# daqbeagle_shield.net
KiCad netlist of a schematic drawn in EAGLE
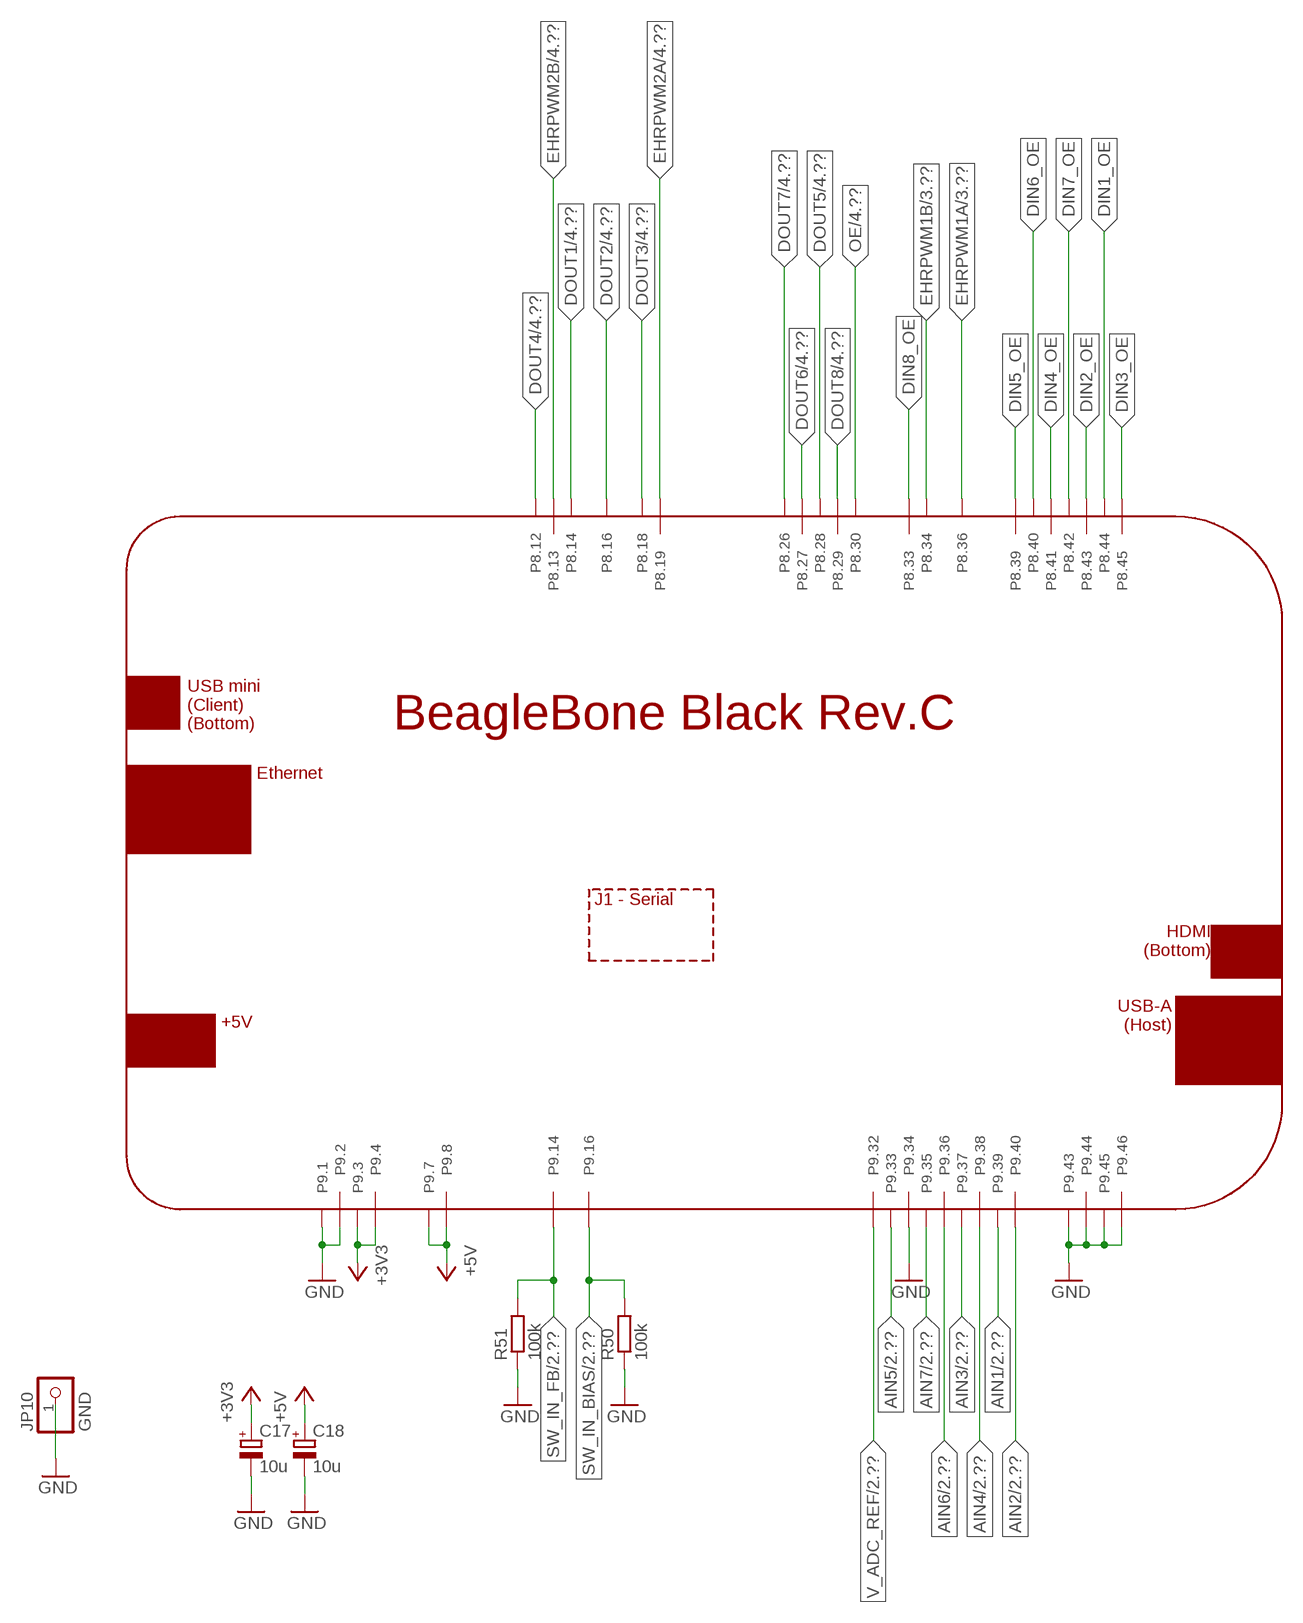
[diagram p0: schematic, sheet 1]
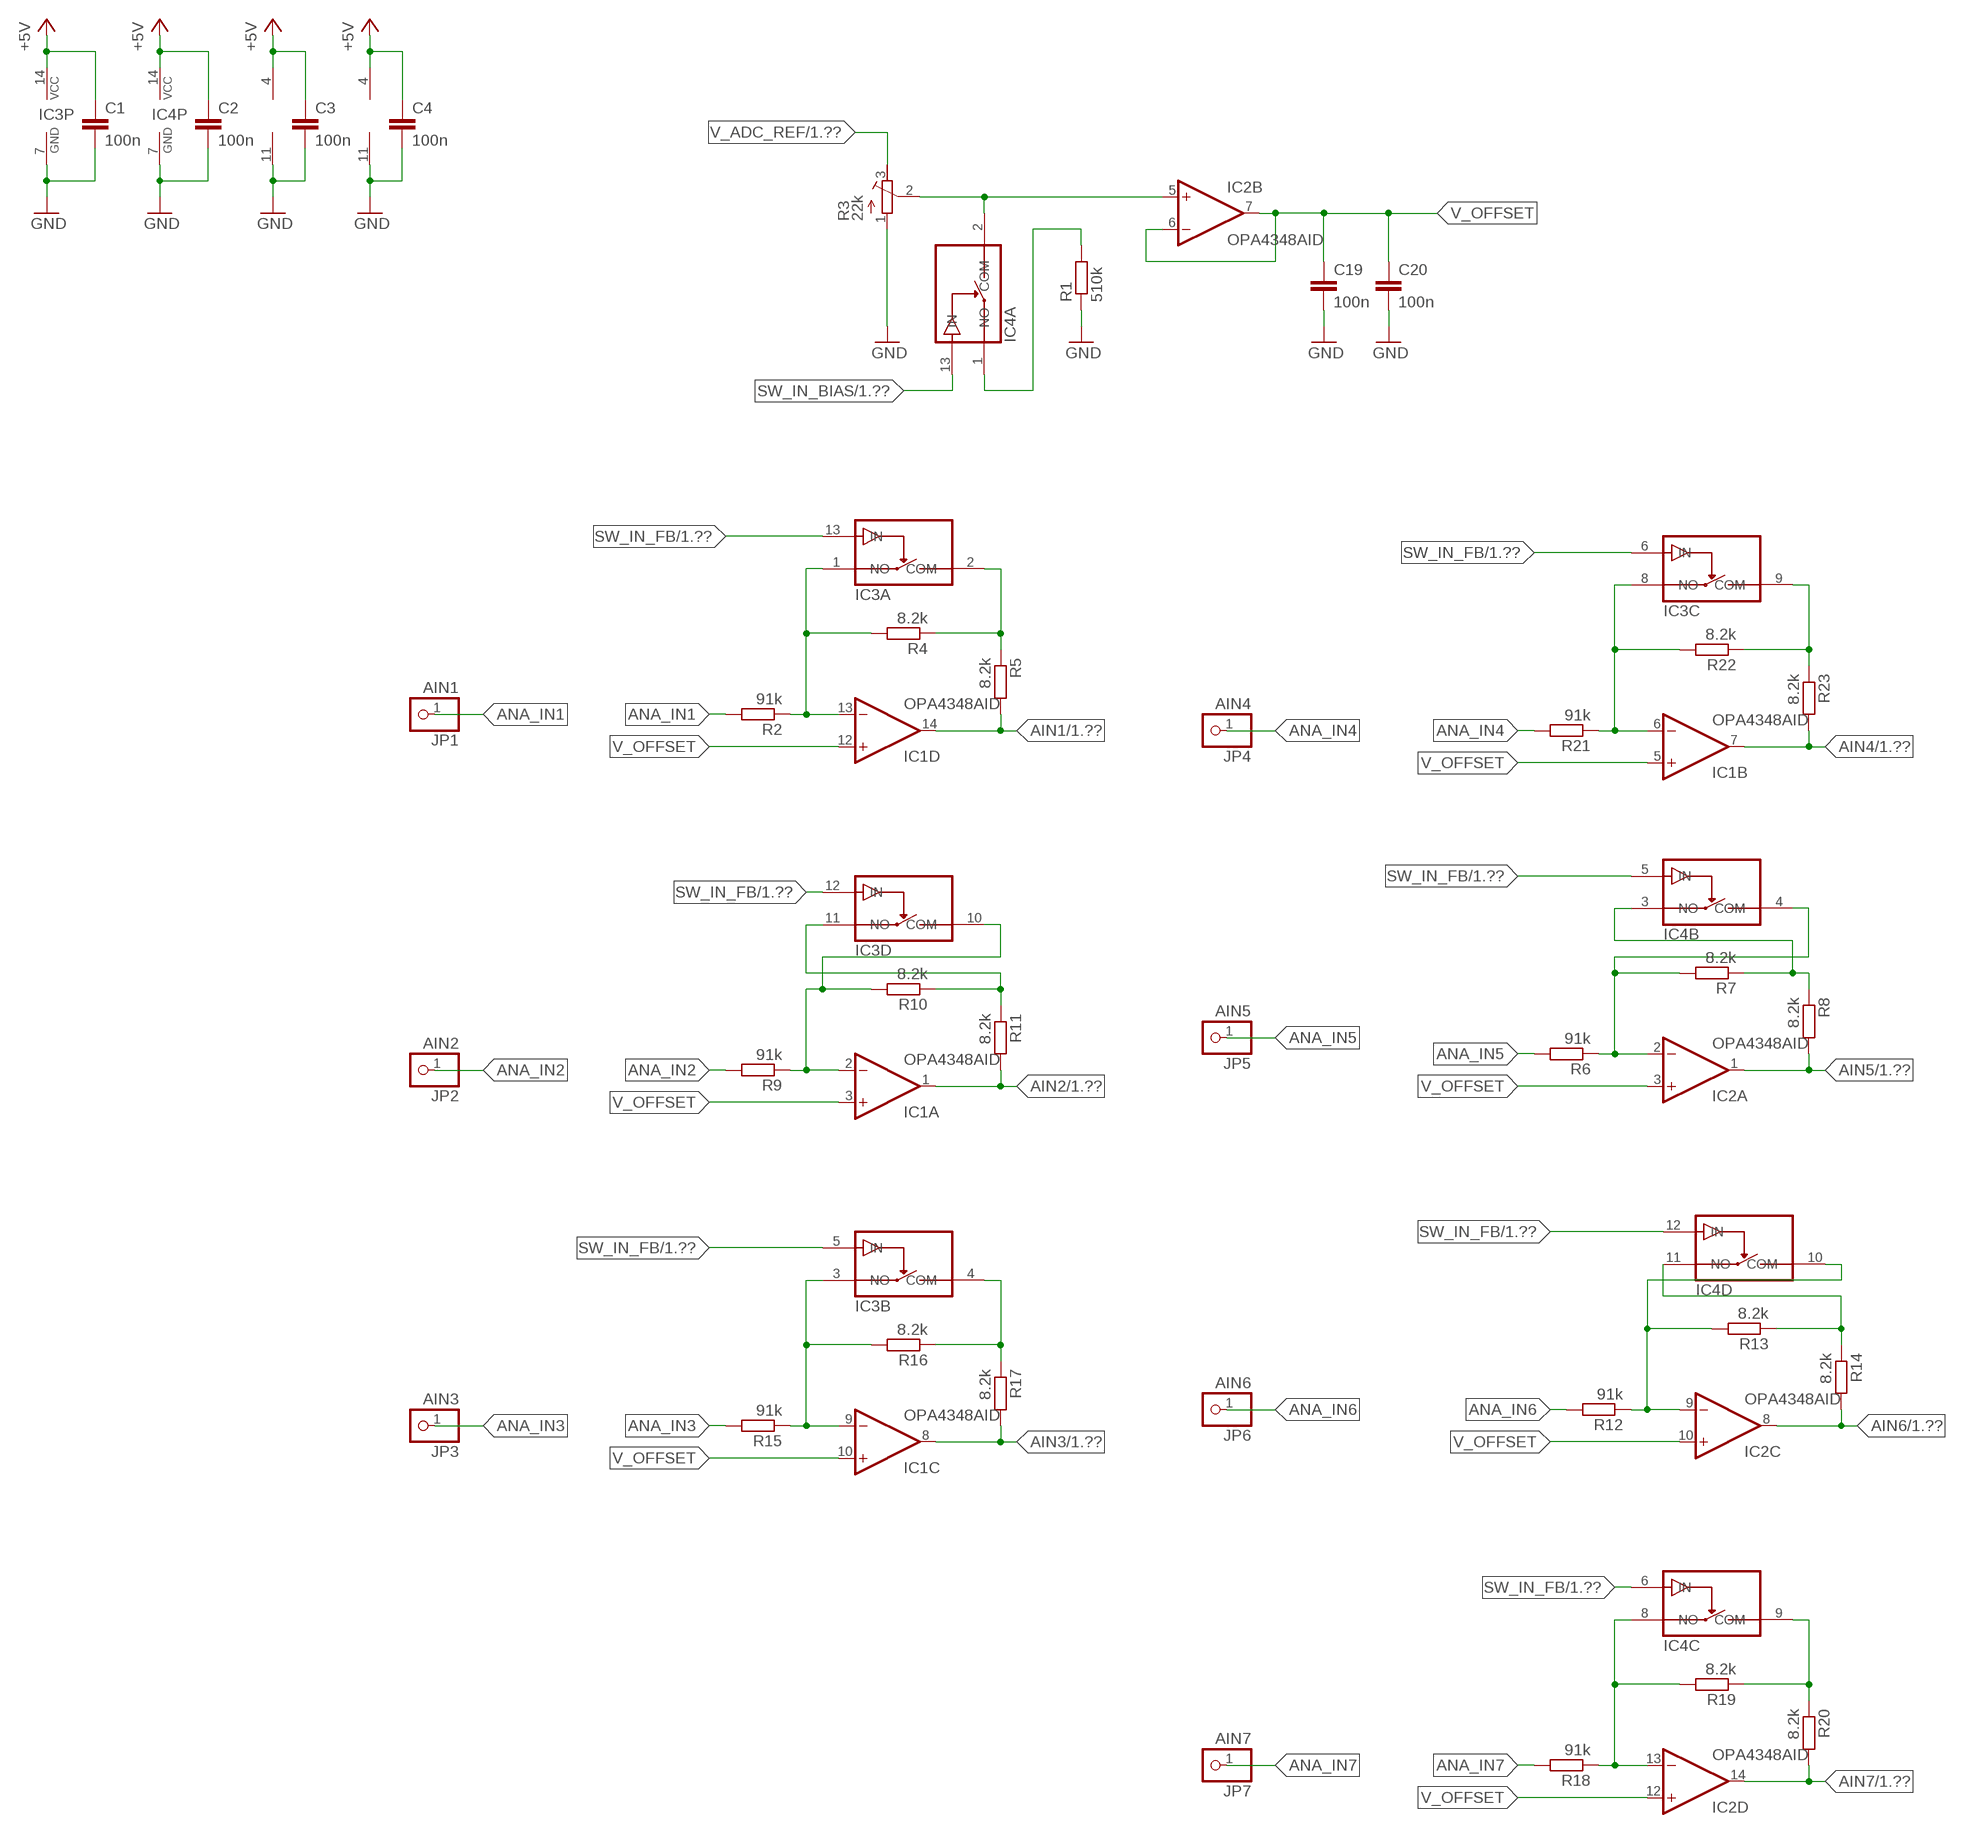
[diagram p1: schematic, sheet 2]
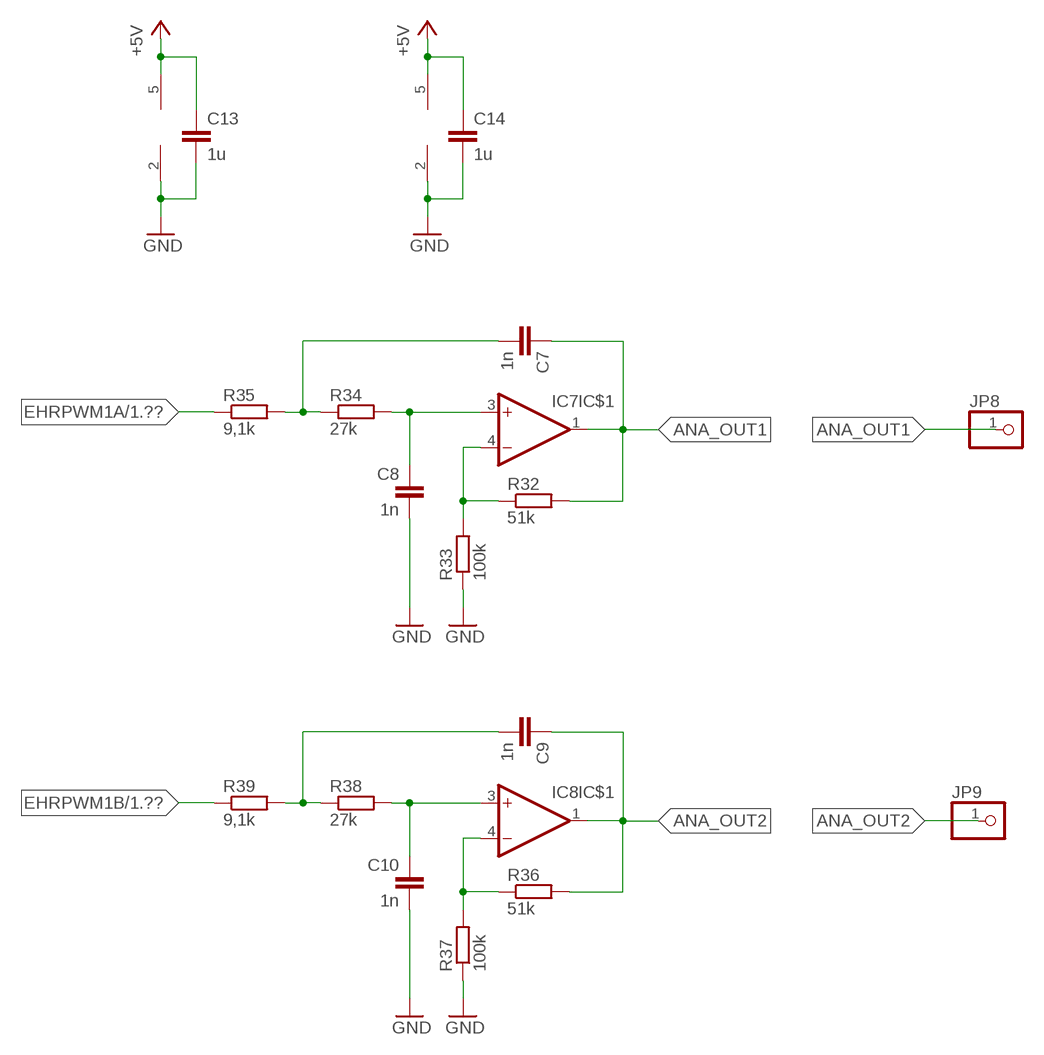
[diagram p2: schematic, sheet 3]
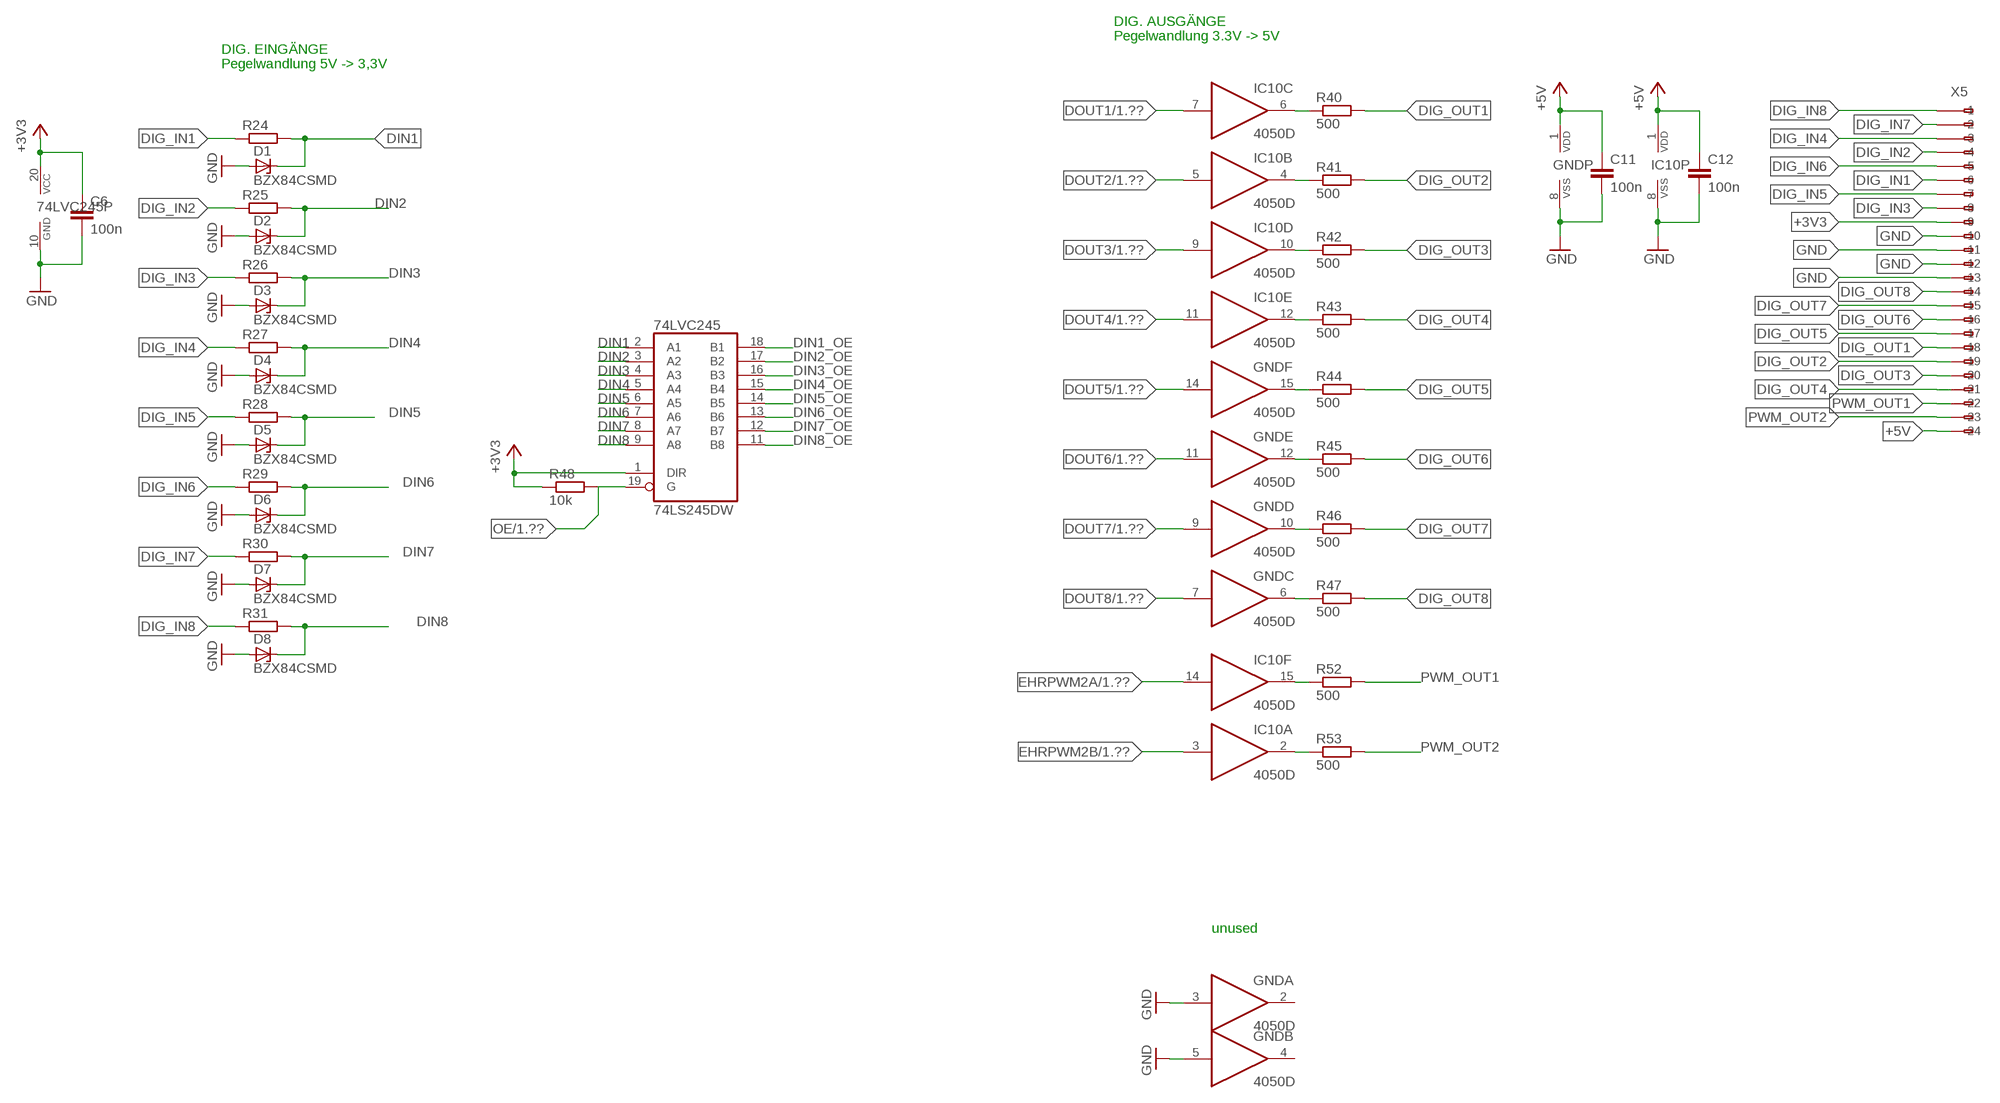
[diagram p3: schematic, sheet 4]

(export (version "E")
  (design (tool "Eeschema 10.0.6"))
  (components
    (comp (ref "C1")
      (value "100n")
      (footprint "eagle-import:C0805")
      (libsource (lib "eagle-import") (part "C-EUC0805"))
    )
    (comp (ref "C2")
      (value "100n")
      (footprint "eagle-import:C0805")
      (libsource (lib "eagle-import") (part "C-EUC0805"))
    )
    (comp (ref "C3")
      (value "100n")
      (footprint "eagle-import:C0805")
      (libsource (lib "eagle-import") (part "C-EUC0805"))
    )
    (comp (ref "C4")
      (value "100n")
      (footprint "eagle-import:C0805")
      (libsource (lib "eagle-import") (part "C-EUC0805"))
    )
    (comp (ref "C19")
      (value "100n")
      (footprint "eagle-import:C0805")
      (libsource (lib "eagle-import") (part "C-EUC0805"))
    )
    (comp (ref "C20")
      (value "100n")
      (footprint "eagle-import:C0805")
      (libsource (lib "eagle-import") (part "C-EUC0805"))
    )
    (comp (ref "IC1")
      (value "OPA4348AID")
      (footprint "eagle-import:SO14")
      (libsource (lib "eagle-import") (part "OPA4348AID"))
    )
    (comp (ref "IC2")
      (value "OPA4348AID")
      (footprint "eagle-import:SO14")
      (libsource (lib "eagle-import") (part "OPA4348AID"))
    )
    (comp (ref "IC3")
      (value "TS12A44514PW")
      (footprint "eagle-import:TSSOP14")
      (libsource (lib "eagle-import") (part "TS12A44514PW"))
    )
    (comp (ref "IC4")
      (value "TS12A44514PW")
      (footprint "eagle-import:TSSOP14")
      (libsource (lib "eagle-import") (part "TS12A44514PW"))
    )
    (comp (ref "JP1")
      (value "AIN1")
      (footprint "eagle-import:PAD")
      (libsource (lib "eagle-import") (part "SOLDER_PAD"))
    )
    (comp (ref "JP2")
      (value "AIN2")
      (footprint "eagle-import:PAD")
      (libsource (lib "eagle-import") (part "SOLDER_PAD"))
    )
    (comp (ref "JP3")
      (value "AIN3")
      (footprint "eagle-import:PAD")
      (libsource (lib "eagle-import") (part "SOLDER_PAD"))
    )
    (comp (ref "JP4")
      (value "AIN4")
      (footprint "eagle-import:PAD")
      (libsource (lib "eagle-import") (part "SOLDER_PAD"))
    )
    (comp (ref "JP5")
      (value "AIN5")
      (footprint "eagle-import:PAD")
      (libsource (lib "eagle-import") (part "SOLDER_PAD"))
    )
    (comp (ref "JP6")
      (value "AIN6")
      (footprint "eagle-import:PAD")
      (libsource (lib "eagle-import") (part "SOLDER_PAD"))
    )
    (comp (ref "JP7")
      (value "AIN7")
      (footprint "eagle-import:PAD")
      (libsource (lib "eagle-import") (part "SOLDER_PAD"))
    )
    (comp (ref "R1")
      (value "510k")
      (footprint "eagle-import:R0603")
      (libsource (lib "eagle-import") (part "R-EU_R0603"))
    )
    (comp (ref "R2")
      (value "91k")
      (footprint "eagle-import:R0603")
      (libsource (lib "eagle-import") (part "R-EU_R0603"))
    )
    (comp (ref "R3")
      (value "22k")
      (footprint "eagle-import:RTRIM3296P")
      (libsource (lib "eagle-import") (part "R-TRIMM"))
    )
    (comp (ref "R4")
      (value "8.2k")
      (footprint "eagle-import:R0603")
      (libsource (lib "eagle-import") (part "R-EU_R0603"))
    )
    (comp (ref "R5")
      (value "8.2k")
      (footprint "eagle-import:R0603")
      (libsource (lib "eagle-import") (part "R-EU_R0603"))
    )
    (comp (ref "R6")
      (value "91k")
      (footprint "eagle-import:R0603")
      (libsource (lib "eagle-import") (part "R-EU_R0603"))
    )
    (comp (ref "R7")
      (value "8.2k")
      (footprint "eagle-import:R0603")
      (libsource (lib "eagle-import") (part "R-EU_R0603"))
    )
    (comp (ref "R8")
      (value "8.2k")
      (footprint "eagle-import:R0603")
      (libsource (lib "eagle-import") (part "R-EU_R0603"))
    )
    (comp (ref "R9")
      (value "91k")
      (footprint "eagle-import:R0603")
      (libsource (lib "eagle-import") (part "R-EU_R0603"))
    )
    (comp (ref "R10")
      (value "8.2k")
      (footprint "eagle-import:R0603")
      (libsource (lib "eagle-import") (part "R-EU_R0603"))
    )
    (comp (ref "R11")
      (value "8.2k")
      (footprint "eagle-import:R0603")
      (libsource (lib "eagle-import") (part "R-EU_R0603"))
    )
    (comp (ref "R12")
      (value "91k")
      (footprint "eagle-import:R0603")
      (libsource (lib "eagle-import") (part "R-EU_R0603"))
    )
    (comp (ref "R13")
      (value "8.2k")
      (footprint "eagle-import:R0603")
      (libsource (lib "eagle-import") (part "R-EU_R0603"))
    )
    (comp (ref "R14")
      (value "8.2k")
      (footprint "eagle-import:R0603")
      (libsource (lib "eagle-import") (part "R-EU_R0603"))
    )
    (comp (ref "R15")
      (value "91k")
      (footprint "eagle-import:R0603")
      (libsource (lib "eagle-import") (part "R-EU_R0603"))
    )
    (comp (ref "R16")
      (value "8.2k")
      (footprint "eagle-import:R0603")
      (libsource (lib "eagle-import") (part "R-EU_R0603"))
    )
    (comp (ref "R17")
      (value "8.2k")
      (footprint "eagle-import:R0603")
      (libsource (lib "eagle-import") (part "R-EU_R0603"))
    )
    (comp (ref "R18")
      (value "91k")
      (footprint "eagle-import:R0603")
      (libsource (lib "eagle-import") (part "R-EU_R0603"))
    )
    (comp (ref "R19")
      (value "8.2k")
      (footprint "eagle-import:R0603")
      (libsource (lib "eagle-import") (part "R-EU_R0603"))
    )
    (comp (ref "R20")
      (value "8.2k")
      (footprint "eagle-import:R0603")
      (libsource (lib "eagle-import") (part "R-EU_R0603"))
    )
    (comp (ref "R21")
      (value "91k")
      (footprint "eagle-import:R0603")
      (libsource (lib "eagle-import") (part "R-EU_R0603"))
    )
    (comp (ref "R22")
      (value "8.2k")
      (footprint "eagle-import:R0603")
      (libsource (lib "eagle-import") (part "R-EU_R0603"))
    )
    (comp (ref "R23")
      (value "8.2k")
      (footprint "eagle-import:R0603")
      (libsource (lib "eagle-import") (part "R-EU_R0603"))
    )
    (comp (ref "C7")
      (value "1n")
      (footprint "eagle-import:C0805")
      (libsource (lib "eagle-import") (part "C-EUC0805"))
    )
    (comp (ref "C8")
      (value "1n")
      (footprint "eagle-import:C0805")
      (libsource (lib "eagle-import") (part "C-EUC0805"))
    )
    (comp (ref "C9")
      (value "1n")
      (footprint "eagle-import:C0805")
      (libsource (lib "eagle-import") (part "C-EUC0805"))
    )
    (comp (ref "C10")
      (value "1n")
      (footprint "eagle-import:C0805")
      (libsource (lib "eagle-import") (part "C-EUC0805"))
    )
    (comp (ref "C13")
      (value "1u")
      (footprint "eagle-import:C0805")
      (libsource (lib "eagle-import") (part "C-EUC0805"))
    )
    (comp (ref "C14")
      (value "1u")
      (footprint "eagle-import:C0805")
      (libsource (lib "eagle-import") (part "C-EUC0805"))
    )
    (comp (ref "IC7")
      (value "OPA320")
      (footprint "eagle-import:SOT23-5L")
      (libsource (lib "eagle-import") (part "OPA320"))
    )
    (comp (ref "IC8")
      (value "OPA320")
      (footprint "eagle-import:SOT23-5L")
      (libsource (lib "eagle-import") (part "OPA320"))
    )
    (comp (ref "JP8")
      (value "SOLDER_PAD")
      (footprint "eagle-import:PAD")
      (libsource (lib "eagle-import") (part "SOLDER_PAD"))
    )
    (comp (ref "JP9")
      (value "SOLDER_PAD")
      (footprint "eagle-import:PAD")
      (libsource (lib "eagle-import") (part "SOLDER_PAD"))
    )
    (comp (ref "R32")
      (value "51k")
      (footprint "eagle-import:R0805")
      (libsource (lib "eagle-import") (part "R-EU_R0805"))
    )
    (comp (ref "R33")
      (value "100k")
      (footprint "eagle-import:R0603")
      (libsource (lib "eagle-import") (part "R-EU_R0603"))
    )
    (comp (ref "R34")
      (value "27k")
      (footprint "eagle-import:R0603")
      (libsource (lib "eagle-import") (part "R-EU_R0603"))
    )
    (comp (ref "R35")
      (value "9,1k")
      (footprint "eagle-import:R0805")
      (libsource (lib "eagle-import") (part "R-EU_R0805"))
    )
    (comp (ref "R36")
      (value "51k")
      (footprint "eagle-import:R0805")
      (libsource (lib "eagle-import") (part "R-EU_R0805"))
    )
    (comp (ref "R37")
      (value "100k")
      (footprint "eagle-import:R0603")
      (libsource (lib "eagle-import") (part "R-EU_R0603"))
    )
    (comp (ref "R38")
      (value "27k")
      (footprint "eagle-import:R0603")
      (libsource (lib "eagle-import") (part "R-EU_R0603"))
    )
    (comp (ref "R39")
      (value "9,1k")
      (footprint "eagle-import:R0805")
      (libsource (lib "eagle-import") (part "R-EU_R0805"))
    )
    (comp (ref "74LVC245")
      (value "74LS245DW")
      (footprint "eagle-import:SO20W")
      (libsource (lib "eagle-import") (part "74245DWLS"))
    )
    (comp (ref "C6")
      (value "100n")
      (footprint "eagle-import:C0805")
      (libsource (lib "eagle-import") (part "C-EUC0805"))
    )
    (comp (ref "C11")
      (value "100n")
      (footprint "eagle-import:C0805")
      (libsource (lib "eagle-import") (part "C-EUC0805"))
    )
    (comp (ref "C12")
      (value "100n")
      (footprint "eagle-import:C0805")
      (libsource (lib "eagle-import") (part "C-EUC0805"))
    )
    (comp (ref "D1")
      (value "BZX84CSMD")
      (footprint "eagle-import:TO236")
      (libsource (lib "eagle-import") (part "BZX84CSMD"))
    )
    (comp (ref "D2")
      (value "BZX84CSMD")
      (footprint "eagle-import:TO236")
      (libsource (lib "eagle-import") (part "BZX84CSMD"))
    )
    (comp (ref "D3")
      (value "BZX84CSMD")
      (footprint "eagle-import:TO236")
      (libsource (lib "eagle-import") (part "BZX84CSMD"))
    )
    (comp (ref "D4")
      (value "BZX84CSMD")
      (footprint "eagle-import:TO236")
      (libsource (lib "eagle-import") (part "BZX84CSMD"))
    )
    (comp (ref "D5")
      (value "BZX84CSMD")
      (footprint "eagle-import:TO236")
      (libsource (lib "eagle-import") (part "BZX84CSMD"))
    )
    (comp (ref "D6")
      (value "BZX84CSMD")
      (footprint "eagle-import:TO236")
      (libsource (lib "eagle-import") (part "BZX84CSMD"))
    )
    (comp (ref "D7")
      (value "BZX84CSMD")
      (footprint "eagle-import:TO236")
      (libsource (lib "eagle-import") (part "BZX84CSMD"))
    )
    (comp (ref "D8")
      (value "BZX84CSMD")
      (footprint "eagle-import:TO236")
      (libsource (lib "eagle-import") (part "BZX84CSMD"))
    )
    (comp (ref "GND")
      (value "4050D")
      (footprint "eagle-import:SO16")
      (libsource (lib "eagle-import") (part "4050D"))
    )
    (comp (ref "IC10")
      (value "4050D")
      (footprint "eagle-import:SO16")
      (libsource (lib "eagle-import") (part "4050D"))
    )
    (comp (ref "R24")
      (value "R-EU_R0805")
      (footprint "eagle-import:R0805")
      (libsource (lib "eagle-import") (part "R-EU_R0805"))
    )
    (comp (ref "R25")
      (value "R-EU_R0805")
      (footprint "eagle-import:R0805")
      (libsource (lib "eagle-import") (part "R-EU_R0805"))
    )
    (comp (ref "R26")
      (value "R-EU_R0805")
      (footprint "eagle-import:R0805")
      (libsource (lib "eagle-import") (part "R-EU_R0805"))
    )
    (comp (ref "R27")
      (value "R-EU_R0805")
      (footprint "eagle-import:R0805")
      (libsource (lib "eagle-import") (part "R-EU_R0805"))
    )
    (comp (ref "R28")
      (value "R-EU_R0805")
      (footprint "eagle-import:R0805")
      (libsource (lib "eagle-import") (part "R-EU_R0805"))
    )
    (comp (ref "R29")
      (value "R-EU_R0805")
      (footprint "eagle-import:R0805")
      (libsource (lib "eagle-import") (part "R-EU_R0805"))
    )
    (comp (ref "R30")
      (value "R-EU_R0805")
      (footprint "eagle-import:R0805")
      (libsource (lib "eagle-import") (part "R-EU_R0805"))
    )
    (comp (ref "R31")
      (value "R-EU_R0805")
      (footprint "eagle-import:R0805")
      (libsource (lib "eagle-import") (part "R-EU_R0805"))
    )
    (comp (ref "R40")
      (value "500")
      (footprint "eagle-import:R0805")
      (libsource (lib "eagle-import") (part "R-EU_R0805"))
    )
    (comp (ref "R41")
      (value "500")
      (footprint "eagle-import:R0805")
      (libsource (lib "eagle-import") (part "R-EU_R0805"))
    )
    (comp (ref "R42")
      (value "500")
      (footprint "eagle-import:R0805")
      (libsource (lib "eagle-import") (part "R-EU_R0805"))
    )
    (comp (ref "R43")
      (value "500")
      (footprint "eagle-import:R0805")
      (libsource (lib "eagle-import") (part "R-EU_R0805"))
    )
    (comp (ref "R44")
      (value "500")
      (footprint "eagle-import:R0805")
      (libsource (lib "eagle-import") (part "R-EU_R0805"))
    )
    (comp (ref "R45")
      (value "500")
      (footprint "eagle-import:R0805")
      (libsource (lib "eagle-import") (part "R-EU_R0805"))
    )
    (comp (ref "R46")
      (value "500")
      (footprint "eagle-import:R0805")
      (libsource (lib "eagle-import") (part "R-EU_R0805"))
    )
    (comp (ref "R47")
      (value "500")
      (footprint "eagle-import:R0805")
      (libsource (lib "eagle-import") (part "R-EU_R0805"))
    )
    (comp (ref "R48")
      (value "10k")
      (footprint "eagle-import:R0805")
      (libsource (lib "eagle-import") (part "R-EU_R0805"))
    )
    (comp (ref "R52")
      (value "500")
      (footprint "eagle-import:R0805")
      (libsource (lib "eagle-import") (part "R-EU_R0805"))
    )
    (comp (ref "R53")
      (value "500")
      (footprint "eagle-import:R0805")
      (libsource (lib "eagle-import") (part "R-EU_R0805"))
    )
    (comp (ref "X5")
      (value "233-124")
      (footprint "eagle-import:233-124")
      (libsource (lib "eagle-import") (part "233-124"))
    )
    (comp (ref "C17")
      (value "10u")
      (footprint "eagle-import:CT3216")
      (libsource (lib "eagle-import") (part "CPOL-EUCT3216"))
    )
    (comp (ref "C18")
      (value "10u")
      (footprint "eagle-import:CT6032")
      (libsource (lib "eagle-import") (part "CPOL-EUCT6032"))
    )
    (comp (ref "JP10")
      (value "GND")
      (footprint "eagle-import:PAD")
      (libsource (lib "eagle-import") (part "SOLDER_PAD"))
    )
    (comp (ref "PCB1")
      (value "BEAGLEBONE_BLACK")
      (footprint "eagle-import:BEAGLEBONE_BLACK")
      (libsource (lib "eagle-import") (part "BEAGLEBONE_BLACK"))
    )
    (comp (ref "R50")
      (value "100k")
      (footprint "eagle-import:R0805")
      (libsource (lib "eagle-import") (part "R-EU_R0805"))
    )
    (comp (ref "R51")
      (value "100k")
      (footprint "eagle-import:R0805")
      (libsource (lib "eagle-import") (part "R-EU_R0805"))
    )
  )
  (nets
    (net (code "1") (name "+3V3") (class "Default")
      (node (ref "74LVC245") (pin "1") (pinfunction "DIR_1") (pintype "input"))
      (node (ref "74LVC245") (pin "20") (pinfunction "VCC_20") (pintype "power_in"))
      (node (ref "C17") (pin "+") (pinfunction "+_+") (pintype "passive"))
      (node (ref "C6") (pin "1") (pinfunction "1_1") (pintype "passive"))
      (node (ref "PCB1") (pin "P9.3") (pinfunction "P9.3_P9.3") (pintype "bidirectional"))
      (node (ref "PCB1") (pin "P9.4") (pinfunction "P9.4_P9.4") (pintype "bidirectional"))
      (node (ref "R48") (pin "1") (pinfunction "1_1") (pintype "passive"))
      (node (ref "X5") (pin "A9") (pinfunction "-9_A9") (pintype "passive"))
      (node (ref "X5") (pin "B9") (pinfunction "B-9_B9") (pintype "passive"))
    )
    (net (code "2") (name "+5V") (class "Default")
      (node (ref "C1") (pin "1") (pinfunction "1_1") (pintype "passive"))
      (node (ref "C11") (pin "1") (pinfunction "1_1") (pintype "passive"))
      (node (ref "C12") (pin "1") (pinfunction "1_1") (pintype "passive"))
      (node (ref "C13") (pin "1") (pinfunction "1_1") (pintype "passive"))
      (node (ref "C14") (pin "1") (pinfunction "1_1") (pintype "passive"))
      (node (ref "C18") (pin "+") (pinfunction "+_+") (pintype "passive"))
      (node (ref "C2") (pin "1") (pinfunction "1_1") (pintype "passive"))
      (node (ref "C3") (pin "1") (pinfunction "1_1") (pintype "passive"))
      (node (ref "C4") (pin "1") (pinfunction "1_1") (pintype "passive"))
      (node (ref "GND") (pin "1") (pinfunction "VDD_1") (pintype "power_in"))
      (node (ref "IC1") (pin "4") (pinfunction "V+_4") (pintype "power_in"))
      (node (ref "IC10") (pin "1") (pinfunction "VDD_1") (pintype "power_in"))
      (node (ref "IC2") (pin "4") (pinfunction "V+_4") (pintype "power_in"))
      (node (ref "IC3") (pin "14") (pinfunction "VCC_14") (pintype "power_in"))
      (node (ref "IC4") (pin "14") (pinfunction "VCC_14") (pintype "power_in"))
      (node (ref "IC7") (pin "5") (pinfunction "V+_5") (pintype "power_in"))
      (node (ref "IC8") (pin "5") (pinfunction "V+_5") (pintype "power_in"))
      (node (ref "PCB1") (pin "P9.7") (pinfunction "P9.7_P9.7") (pintype "bidirectional"))
      (node (ref "PCB1") (pin "P9.8") (pinfunction "P9.8_P9.8") (pintype "bidirectional"))
      (node (ref "X5") (pin "A24") (pinfunction "-24_A24") (pintype "passive"))
      (node (ref "X5") (pin "B24") (pinfunction "B-24_B24") (pintype "passive"))
    )
    (net (code "3") (name "AIN1") (class "Default")
      (node (ref "IC1") (pin "14") (pinfunction "OUT_14") (pintype "open_collector"))
      (node (ref "PCB1") (pin "P9.39") (pinfunction "P9.39_P9.39") (pintype "bidirectional"))
      (node (ref "R5") (pin "2") (pinfunction "2_2") (pintype "passive"))
    )
    (net (code "4") (name "AIN2") (class "Default")
      (node (ref "IC1") (pin "1") (pinfunction "OUT_1") (pintype "open_collector"))
      (node (ref "PCB1") (pin "P9.40") (pinfunction "P9.40_P9.40") (pintype "bidirectional"))
      (node (ref "R11") (pin "2") (pinfunction "2_2") (pintype "passive"))
    )
    (net (code "5") (name "AIN3") (class "Default")
      (node (ref "IC1") (pin "8") (pinfunction "OUT_8") (pintype "open_collector"))
      (node (ref "PCB1") (pin "P9.37") (pinfunction "P9.37_P9.37") (pintype "bidirectional"))
      (node (ref "R17") (pin "2") (pinfunction "2_2") (pintype "passive"))
    )
    (net (code "6") (name "AIN4") (class "Default")
      (node (ref "IC1") (pin "7") (pinfunction "OUT_7") (pintype "open_collector"))
      (node (ref "PCB1") (pin "P9.38") (pinfunction "P9.38_P9.38") (pintype "bidirectional"))
      (node (ref "R23") (pin "2") (pinfunction "2_2") (pintype "passive"))
    )
    (net (code "7") (name "AIN5") (class "Default")
      (node (ref "IC2") (pin "1") (pinfunction "OUT_1") (pintype "open_collector"))
      (node (ref "PCB1") (pin "P9.33") (pinfunction "P9.33_P9.33") (pintype "bidirectional"))
      (node (ref "R8") (pin "2") (pinfunction "2_2") (pintype "passive"))
    )
    (net (code "8") (name "AIN6") (class "Default")
      (node (ref "IC2") (pin "8") (pinfunction "OUT_8") (pintype "open_collector"))
      (node (ref "PCB1") (pin "P9.36") (pinfunction "P9.36_P9.36") (pintype "bidirectional"))
      (node (ref "R14") (pin "2") (pinfunction "2_2") (pintype "passive"))
    )
    (net (code "9") (name "AIN7") (class "Default")
      (node (ref "IC2") (pin "14") (pinfunction "OUT_14") (pintype "open_collector"))
      (node (ref "PCB1") (pin "P9.35") (pinfunction "P9.35_P9.35") (pintype "bidirectional"))
      (node (ref "R20") (pin "2") (pinfunction "2_2") (pintype "passive"))
    )
    (net (code "10") (name "ANA_IN1") (class "Default")
      (node (ref "JP1") (pin "1") (pinfunction "1_1") (pintype "passive"))
      (node (ref "R2") (pin "2") (pinfunction "2_2") (pintype "passive"))
    )
    (net (code "11") (name "ANA_IN2") (class "Default")
      (node (ref "JP2") (pin "1") (pinfunction "1_1") (pintype "passive"))
      (node (ref "R9") (pin "2") (pinfunction "2_2") (pintype "passive"))
    )
    (net (code "12") (name "ANA_IN3") (class "Default")
      (node (ref "JP3") (pin "1") (pinfunction "1_1") (pintype "passive"))
      (node (ref "R15") (pin "2") (pinfunction "2_2") (pintype "passive"))
    )
    (net (code "13") (name "ANA_IN4") (class "Default")
      (node (ref "JP4") (pin "1") (pinfunction "1_1") (pintype "passive"))
      (node (ref "R21") (pin "2") (pinfunction "2_2") (pintype "passive"))
    )
    (net (code "14") (name "ANA_IN5") (class "Default")
      (node (ref "JP5") (pin "1") (pinfunction "1_1") (pintype "passive"))
      (node (ref "R6") (pin "2") (pinfunction "2_2") (pintype "passive"))
    )
    (net (code "15") (name "ANA_IN6") (class "Default")
      (node (ref "JP6") (pin "1") (pinfunction "1_1") (pintype "passive"))
      (node (ref "R12") (pin "2") (pinfunction "2_2") (pintype "passive"))
    )
    (net (code "16") (name "ANA_IN7") (class "Default")
      (node (ref "JP7") (pin "1") (pinfunction "1_1") (pintype "passive"))
      (node (ref "R18") (pin "2") (pinfunction "2_2") (pintype "passive"))
    )
    (net (code "17") (name "ANA_OUT1") (class "Default")
      (node (ref "C7") (pin "1") (pinfunction "1_1") (pintype "passive"))
      (node (ref "IC7") (pin "1") (pinfunction "OUT_1") (pintype "open_collector"))
      (node (ref "JP8") (pin "1") (pinfunction "1_1") (pintype "passive"))
      (node (ref "R32") (pin "2") (pinfunction "2_2") (pintype "passive"))
    )
    (net (code "18") (name "ANA_OUT2") (class "Default")
      (node (ref "C9") (pin "1") (pinfunction "1_1") (pintype "passive"))
      (node (ref "IC8") (pin "1") (pinfunction "OUT_1") (pintype "open_collector"))
      (node (ref "JP9") (pin "1") (pinfunction "1_1") (pintype "passive"))
      (node (ref "R36") (pin "2") (pinfunction "2_2") (pintype "passive"))
    )
    (net (code "19") (name "DIG_IN1") (class "Default")
      (node (ref "R24") (pin "1") (pinfunction "1_1") (pintype "passive"))
      (node (ref "X5") (pin "A6") (pinfunction "-6_A6") (pintype "passive"))
    )
    (net (code "20") (name "DIG_IN2") (class "Default")
      (node (ref "R25") (pin "1") (pinfunction "1_1") (pintype "passive"))
      (node (ref "X5") (pin "A4") (pinfunction "-4_A4") (pintype "passive"))
    )
    (net (code "21") (name "DIG_IN3") (class "Default")
      (node (ref "R26") (pin "1") (pinfunction "1_1") (pintype "passive"))
      (node (ref "X5") (pin "A8") (pinfunction "-8_A8") (pintype "passive"))
    )
    (net (code "22") (name "DIG_IN4") (class "Default")
      (node (ref "R27") (pin "1") (pinfunction "1_1") (pintype "passive"))
      (node (ref "X5") (pin "A3") (pinfunction "-3_A3") (pintype "passive"))
    )
    (net (code "23") (name "DIG_IN5") (class "Default")
      (node (ref "R28") (pin "1") (pinfunction "1_1") (pintype "passive"))
      (node (ref "X5") (pin "A7") (pinfunction "-7_A7") (pintype "passive"))
    )
    (net (code "24") (name "DIG_IN6") (class "Default")
      (node (ref "R29") (pin "1") (pinfunction "1_1") (pintype "passive"))
      (node (ref "X5") (pin "A5") (pinfunction "-5_A5") (pintype "passive"))
    )
    (net (code "25") (name "DIG_IN7") (class "Default")
      (node (ref "R30") (pin "1") (pinfunction "1_1") (pintype "passive"))
      (node (ref "X5") (pin "A2") (pinfunction "-2_A2") (pintype "passive"))
    )
    (net (code "26") (name "DIG_IN8") (class "Default")
      (node (ref "R31") (pin "1") (pinfunction "1_1") (pintype "passive"))
      (node (ref "X5") (pin "A1") (pinfunction "-1_A1") (pintype "passive"))
    )
    (net (code "27") (name "DIG_OUT1") (class "Default")
      (node (ref "R40") (pin "2") (pinfunction "2_2") (pintype "passive"))
      (node (ref "X5") (pin "A18") (pinfunction "-18_A18") (pintype "passive"))
      (node (ref "X5") (pin "B18") (pinfunction "B-18_B18") (pintype "passive"))
    )
    (net (code "28") (name "DIG_OUT2") (class "Default")
      (node (ref "R41") (pin "2") (pinfunction "2_2") (pintype "passive"))
      (node (ref "X5") (pin "A19") (pinfunction "-19_A19") (pintype "passive"))
      (node (ref "X5") (pin "B19") (pinfunction "B-19_B19") (pintype "passive"))
    )
    (net (code "29") (name "DIG_OUT3") (class "Default")
      (node (ref "R42") (pin "2") (pinfunction "2_2") (pintype "passive"))
      (node (ref "X5") (pin "A20") (pinfunction "-20_A20") (pintype "passive"))
      (node (ref "X5") (pin "B20") (pinfunction "B-20_B20") (pintype "passive"))
    )
    (net (code "30") (name "DIG_OUT4") (class "Default")
      (node (ref "R43") (pin "2") (pinfunction "2_2") (pintype "passive"))
      (node (ref "X5") (pin "A21") (pinfunction "-21_A21") (pintype "passive"))
      (node (ref "X5") (pin "B21") (pinfunction "B-21_B21") (pintype "passive"))
    )
    (net (code "31") (name "DIG_OUT5") (class "Default")
      (node (ref "R44") (pin "2") (pinfunction "2_2") (pintype "passive"))
      (node (ref "X5") (pin "A17") (pinfunction "-17_A17") (pintype "passive"))
      (node (ref "X5") (pin "B17") (pinfunction "B-17_B17") (pintype "passive"))
    )
    (net (code "32") (name "DIG_OUT6") (class "Default")
      (node (ref "R45") (pin "2") (pinfunction "2_2") (pintype "passive"))
      (node (ref "X5") (pin "A16") (pinfunction "-16_A16") (pintype "passive"))
      (node (ref "X5") (pin "B16") (pinfunction "B-16_B16") (pintype "passive"))
    )
    (net (code "33") (name "DIG_OUT7") (class "Default")
      (node (ref "R46") (pin "2") (pinfunction "2_2") (pintype "passive"))
      (node (ref "X5") (pin "A15") (pinfunction "-15_A15") (pintype "passive"))
      (node (ref "X5") (pin "B15") (pinfunction "B-15_B15") (pintype "passive"))
    )
    (net (code "34") (name "DIG_OUT8") (class "Default")
      (node (ref "R47") (pin "2") (pinfunction "2_2") (pintype "passive"))
      (node (ref "X5") (pin "A14") (pinfunction "-14_A14") (pintype "passive"))
      (node (ref "X5") (pin "B14") (pinfunction "B-14_B14") (pintype "passive"))
    )
    (net (code "35") (name "DIN1") (class "Default")
      (node (ref "74LVC245") (pin "2") (pinfunction "A1_2") (pintype "bidirectional"))
      (node (ref "D1") (pin "C") (pinfunction "C_C") (pintype "passive"))
      (node (ref "R24") (pin "2") (pinfunction "2_2") (pintype "passive"))
    )
    (net (code "36") (name "DIN1_OE") (class "Default")
      (node (ref "74LVC245") (pin "18") (pinfunction "B1_18") (pintype "bidirectional"))
      (node (ref "PCB1") (pin "P8.44") (pinfunction "P8.44_P8.44") (pintype "bidirectional"))
    )
    (net (code "37") (name "DIN2") (class "Default")
      (node (ref "74LVC245") (pin "3") (pinfunction "A2_3") (pintype "bidirectional"))
      (node (ref "D2") (pin "C") (pinfunction "C_C") (pintype "passive"))
      (node (ref "R25") (pin "2") (pinfunction "2_2") (pintype "passive"))
    )
    (net (code "38") (name "DIN2_OE") (class "Default")
      (node (ref "74LVC245") (pin "17") (pinfunction "B2_17") (pintype "bidirectional"))
      (node (ref "PCB1") (pin "P8.43") (pinfunction "P8.43_P8.43") (pintype "bidirectional"))
    )
    (net (code "39") (name "DIN3") (class "Default")
      (node (ref "74LVC245") (pin "4") (pinfunction "A3_4") (pintype "bidirectional"))
      (node (ref "D3") (pin "C") (pinfunction "C_C") (pintype "passive"))
      (node (ref "R26") (pin "2") (pinfunction "2_2") (pintype "passive"))
    )
    (net (code "40") (name "DIN3_OE") (class "Default")
      (node (ref "74LVC245") (pin "16") (pinfunction "B3_16") (pintype "bidirectional"))
      (node (ref "PCB1") (pin "P8.45") (pinfunction "P8.45_P8.45") (pintype "bidirectional"))
    )
    (net (code "41") (name "DIN4") (class "Default")
      (node (ref "74LVC245") (pin "5") (pinfunction "A4_5") (pintype "bidirectional"))
      (node (ref "D4") (pin "C") (pinfunction "C_C") (pintype "passive"))
      (node (ref "R27") (pin "2") (pinfunction "2_2") (pintype "passive"))
    )
    (net (code "42") (name "DIN4_OE") (class "Default")
      (node (ref "74LVC245") (pin "15") (pinfunction "B4_15") (pintype "bidirectional"))
      (node (ref "PCB1") (pin "P8.41") (pinfunction "P8.41_P8.41") (pintype "bidirectional"))
    )
    (net (code "43") (name "DIN5") (class "Default")
      (node (ref "74LVC245") (pin "6") (pinfunction "A5_6") (pintype "bidirectional"))
      (node (ref "D5") (pin "C") (pinfunction "C_C") (pintype "passive"))
      (node (ref "R28") (pin "2") (pinfunction "2_2") (pintype "passive"))
    )
    (net (code "44") (name "DIN5_OE") (class "Default")
      (node (ref "74LVC245") (pin "14") (pinfunction "B5_14") (pintype "bidirectional"))
      (node (ref "PCB1") (pin "P8.39") (pinfunction "P8.39_P8.39") (pintype "bidirectional"))
    )
    (net (code "45") (name "DIN6") (class "Default")
      (node (ref "74LVC245") (pin "7") (pinfunction "A6_7") (pintype "bidirectional"))
      (node (ref "D6") (pin "C") (pinfunction "C_C") (pintype "passive"))
      (node (ref "R29") (pin "2") (pinfunction "2_2") (pintype "passive"))
    )
    (net (code "46") (name "DIN6_OE") (class "Default")
      (node (ref "74LVC245") (pin "13") (pinfunction "B6_13") (pintype "bidirectional"))
      (node (ref "PCB1") (pin "P8.40") (pinfunction "P8.40_P8.40") (pintype "bidirectional"))
    )
    (net (code "47") (name "DIN7") (class "Default")
      (node (ref "74LVC245") (pin "8") (pinfunction "A7_8") (pintype "bidirectional"))
      (node (ref "D7") (pin "C") (pinfunction "C_C") (pintype "passive"))
      (node (ref "R30") (pin "2") (pinfunction "2_2") (pintype "passive"))
    )
    (net (code "48") (name "DIN7_OE") (class "Default")
      (node (ref "74LVC245") (pin "12") (pinfunction "B7_12") (pintype "bidirectional"))
      (node (ref "PCB1") (pin "P8.42") (pinfunction "P8.42_P8.42") (pintype "bidirectional"))
    )
    (net (code "49") (name "DIN8") (class "Default")
      (node (ref "74LVC245") (pin "9") (pinfunction "A8_9") (pintype "bidirectional"))
      (node (ref "D8") (pin "C") (pinfunction "C_C") (pintype "passive"))
      (node (ref "R31") (pin "2") (pinfunction "2_2") (pintype "passive"))
    )
    (net (code "50") (name "DIN8_OE") (class "Default")
      (node (ref "74LVC245") (pin "11") (pinfunction "B8_11") (pintype "bidirectional"))
      (node (ref "PCB1") (pin "P8.33") (pinfunction "P8.33_P8.33") (pintype "bidirectional"))
    )
    (net (code "51") (name "DOUT1") (class "Default")
      (node (ref "IC10") (pin "7") (pinfunction "I_7") (pintype "input"))
      (node (ref "PCB1") (pin "P8.14") (pinfunction "P8.14_P8.14") (pintype "bidirectional"))
    )
    (net (code "52") (name "DOUT2") (class "Default")
      (node (ref "IC10") (pin "5") (pinfunction "I_5") (pintype "input"))
      (node (ref "PCB1") (pin "P8.16") (pinfunction "P8.16_P8.16") (pintype "bidirectional"))
    )
    (net (code "53") (name "DOUT3") (class "Default")
      (node (ref "IC10") (pin "9") (pinfunction "I_9") (pintype "input"))
      (node (ref "PCB1") (pin "P8.18") (pinfunction "P8.18_P8.18") (pintype "bidirectional"))
    )
    (net (code "54") (name "DOUT4") (class "Default")
      (node (ref "IC10") (pin "11") (pinfunction "I_11") (pintype "input"))
      (node (ref "PCB1") (pin "P8.12") (pinfunction "P8.12_P8.12") (pintype "bidirectional"))
    )
    (net (code "55") (name "DOUT5") (class "Default")
      (node (ref "GND") (pin "14") (pinfunction "I_14") (pintype "input"))
      (node (ref "PCB1") (pin "P8.28") (pinfunction "P8.28_P8.28") (pintype "bidirectional"))
    )
    (net (code "56") (name "DOUT6") (class "Default")
      (node (ref "GND") (pin "11") (pinfunction "I_11") (pintype "input"))
      (node (ref "PCB1") (pin "P8.27") (pinfunction "P8.27_P8.27") (pintype "bidirectional"))
    )
    (net (code "57") (name "DOUT7") (class "Default")
      (node (ref "GND") (pin "9") (pinfunction "I_9") (pintype "input"))
      (node (ref "PCB1") (pin "P8.26") (pinfunction "P8.26_P8.26") (pintype "bidirectional"))
    )
    (net (code "58") (name "DOUT8") (class "Default")
      (node (ref "GND") (pin "7") (pinfunction "I_7") (pintype "input"))
      (node (ref "PCB1") (pin "P8.29") (pinfunction "P8.29_P8.29") (pintype "bidirectional"))
    )
    (net (code "59") (name "EHRPWM1A") (class "Default")
      (node (ref "PCB1") (pin "P8.36") (pinfunction "P8.36_P8.36") (pintype "bidirectional"))
      (node (ref "R35") (pin "1") (pinfunction "1_1") (pintype "passive"))
    )
    (net (code "60") (name "EHRPWM1B") (class "Default")
      (node (ref "PCB1") (pin "P8.34") (pinfunction "P8.34_P8.34") (pintype "bidirectional"))
      (node (ref "R39") (pin "1") (pinfunction "1_1") (pintype "passive"))
    )
    (net (code "61") (name "EHRPWM2A") (class "Default")
      (node (ref "IC10") (pin "14") (pinfunction "I_14") (pintype "input"))
      (node (ref "PCB1") (pin "P8.19") (pinfunction "P8.19_P8.19") (pintype "bidirectional"))
    )
    (net (code "62") (name "EHRPWM2B") (class "Default")
      (node (ref "IC10") (pin "3") (pinfunction "I_3") (pintype "input"))
      (node (ref "PCB1") (pin "P8.13") (pinfunction "P8.13_P8.13") (pintype "bidirectional"))
    )
    (net (code "63") (name "GND") (class "Default")
      (node (ref "74LVC245") (pin "10") (pinfunction "GND_10") (pintype "power_in"))
      (node (ref "C1") (pin "2") (pinfunction "2_2") (pintype "passive"))
      (node (ref "C10") (pin "2") (pinfunction "2_2") (pintype "passive"))
      (node (ref "C11") (pin "2") (pinfunction "2_2") (pintype "passive"))
      (node (ref "C12") (pin "2") (pinfunction "2_2") (pintype "passive"))
      (node (ref "C13") (pin "2") (pinfunction "2_2") (pintype "passive"))
      (node (ref "C14") (pin "2") (pinfunction "2_2") (pintype "passive"))
      (node (ref "C17") (pin "-") (pinfunction "-_-") (pintype "passive"))
      (node (ref "C18") (pin "-") (pinfunction "-_-") (pintype "passive"))
      (node (ref "C19") (pin "2") (pinfunction "2_2") (pintype "passive"))
      (node (ref "C2") (pin "2") (pinfunction "2_2") (pintype "passive"))
      (node (ref "C20") (pin "2") (pinfunction "2_2") (pintype "passive"))
      (node (ref "C3") (pin "2") (pinfunction "2_2") (pintype "passive"))
      (node (ref "C4") (pin "2") (pinfunction "2_2") (pintype "passive"))
      (node (ref "C6") (pin "2") (pinfunction "2_2") (pintype "passive"))
      (node (ref "C8") (pin "2") (pinfunction "2_2") (pintype "passive"))
      (node (ref "D1") (pin "A") (pinfunction "A_A") (pintype "passive"))
      (node (ref "D2") (pin "A") (pinfunction "A_A") (pintype "passive"))
      (node (ref "D3") (pin "A") (pinfunction "A_A") (pintype "passive"))
      (node (ref "D4") (pin "A") (pinfunction "A_A") (pintype "passive"))
      (node (ref "D5") (pin "A") (pinfunction "A_A") (pintype "passive"))
      (node (ref "D6") (pin "A") (pinfunction "A_A") (pintype "passive"))
      (node (ref "D7") (pin "A") (pinfunction "A_A") (pintype "passive"))
      (node (ref "D8") (pin "A") (pinfunction "A_A") (pintype "passive"))
      (node (ref "GND") (pin "3") (pinfunction "I_3") (pintype "input"))
      (node (ref "GND") (pin "5") (pinfunction "I_5") (pintype "input"))
      (node (ref "GND") (pin "8") (pinfunction "VSS_8") (pintype "power_in"))
      (node (ref "IC1") (pin "11") (pinfunction "GND_11") (pintype "power_in"))
      (node (ref "IC10") (pin "8") (pinfunction "VSS_8") (pintype "power_in"))
      (node (ref "IC2") (pin "11") (pinfunction "GND_11") (pintype "power_in"))
      (node (ref "IC3") (pin "7") (pinfunction "GND_7") (pintype "power_in"))
      (node (ref "IC4") (pin "7") (pinfunction "GND_7") (pintype "power_in"))
      (node (ref "IC7") (pin "2") (pinfunction "GND_2") (pintype "power_in"))
      (node (ref "IC8") (pin "2") (pinfunction "GND_2") (pintype "power_in"))
      (node (ref "JP10") (pin "1") (pinfunction "1_1") (pintype "passive"))
      (node (ref "PCB1") (pin "P9.1") (pinfunction "P9.1_P9.1") (pintype "bidirectional"))
      (node (ref "PCB1") (pin "P9.2") (pinfunction "P9.2_P9.2") (pintype "bidirectional"))
      (node (ref "PCB1") (pin "P9.34") (pinfunction "P9.34_P9.34") (pintype "bidirectional"))
      (node (ref "PCB1") (pin "P9.43") (pinfunction "P9.43_P9.43") (pintype "bidirectional"))
      (node (ref "PCB1") (pin "P9.44") (pinfunction "P9.44_P9.44") (pintype "bidirectional"))
      (node (ref "PCB1") (pin "P9.45") (pinfunction "P9.45_P9.45") (pintype "bidirectional"))
      (node (ref "PCB1") (pin "P9.46") (pinfunction "P9.46_P9.46") (pintype "bidirectional"))
      (node (ref "R1") (pin "1") (pinfunction "1_1") (pintype "passive"))
      (node (ref "R3") (pin "1") (pinfunction "A_1") (pintype "passive"))
      (node (ref "R33") (pin "1") (pinfunction "1_1") (pintype "passive"))
      (node (ref "R37") (pin "1") (pinfunction "1_1") (pintype "passive"))
      (node (ref "R50") (pin "1") (pinfunction "1_1") (pintype "passive"))
      (node (ref "R51") (pin "1") (pinfunction "1_1") (pintype "passive"))
      (node (ref "X5") (pin "A10") (pinfunction "-10_A10") (pintype "passive"))
      (node (ref "X5") (pin "A11") (pinfunction "-11_A11") (pintype "passive"))
      (node (ref "X5") (pin "A12") (pinfunction "-12_A12") (pintype "passive"))
      (node (ref "X5") (pin "A13") (pinfunction "-13_A13") (pintype "passive"))
      (node (ref "X5") (pin "B10") (pinfunction "B-10_B10") (pintype "passive"))
      (node (ref "X5") (pin "B11") (pinfunction "B-11_B11") (pintype "passive"))
      (node (ref "X5") (pin "B12") (pinfunction "B-12_B12") (pintype "passive"))
      (node (ref "X5") (pin "B13") (pinfunction "B-13_B13") (pintype "passive"))
    )
    (net (code "64") (name "Net-(C7-Pad2)") (class "Default")
      (node (ref "C7") (pin "2") (pinfunction "2_2") (pintype "passive"))
      (node (ref "R34") (pin "1") (pinfunction "1_1") (pintype "passive"))
      (node (ref "R35") (pin "2") (pinfunction "2_2") (pintype "passive"))
    )
    (net (code "65") (name "Net-(C9-Pad2)") (class "Default")
      (node (ref "C9") (pin "2") (pinfunction "2_2") (pintype "passive"))
      (node (ref "R38") (pin "1") (pinfunction "1_1") (pintype "passive"))
      (node (ref "R39") (pin "2") (pinfunction "2_2") (pintype "passive"))
    )
    (net (code "66") (name "Net-(GNDC-O)") (class "Default")
      (node (ref "GND") (pin "6") (pinfunction "O_6") (pintype "output"))
      (node (ref "R47") (pin "1") (pinfunction "1_1") (pintype "passive"))
    )
    (net (code "67") (name "Net-(GNDD-O)") (class "Default")
      (node (ref "GND") (pin "10") (pinfunction "O_10") (pintype "output"))
      (node (ref "R46") (pin "1") (pinfunction "1_1") (pintype "passive"))
    )
    (net (code "68") (name "Net-(GNDE-O)") (class "Default")
      (node (ref "GND") (pin "12") (pinfunction "O_12") (pintype "output"))
      (node (ref "R45") (pin "1") (pinfunction "1_1") (pintype "passive"))
    )
    (net (code "69") (name "Net-(GNDF-O)") (class "Default")
      (node (ref "GND") (pin "15") (pinfunction "O_15") (pintype "output"))
      (node (ref "R44") (pin "1") (pinfunction "1_1") (pintype "passive"))
    )
    (net (code "70") (name "Net-(IC1A--IN)") (class "Default")
      (node (ref "IC1") (pin "2") (pinfunction "-IN_2") (pintype "input"))
      (node (ref "IC3") (pin "10") (pinfunction "COM_10") (pintype "tri_state"))
      (node (ref "R10") (pin "2") (pinfunction "2_2") (pintype "passive"))
      (node (ref "R9") (pin "1") (pinfunction "1_1") (pintype "passive"))
    )
    (net (code "71") (name "Net-(IC1B--IN)") (class "Default")
      (node (ref "IC1") (pin "6") (pinfunction "-IN_6") (pintype "input"))
      (node (ref "IC3") (pin "8") (pinfunction "NO_8") (pintype "tri_state"))
      (node (ref "R21") (pin "1") (pinfunction "1_1") (pintype "passive"))
      (node (ref "R22") (pin "2") (pinfunction "2_2") (pintype "passive"))
    )
    (net (code "72") (name "Net-(IC1C--IN)") (class "Default")
      (node (ref "IC1") (pin "9") (pinfunction "-IN_9") (pintype "input"))
      (node (ref "IC3") (pin "3") (pinfunction "NO_3") (pintype "tri_state"))
      (node (ref "R15") (pin "1") (pinfunction "1_1") (pintype "passive"))
      (node (ref "R16") (pin "2") (pinfunction "2_2") (pintype "passive"))
    )
    (net (code "73") (name "Net-(IC1D--IN)") (class "Default")
      (node (ref "IC1") (pin "13") (pinfunction "-IN_13") (pintype "input"))
      (node (ref "IC3") (pin "1") (pinfunction "NO_1") (pintype "tri_state"))
      (node (ref "R2") (pin "1") (pinfunction "1_1") (pintype "passive"))
      (node (ref "R4") (pin "2") (pinfunction "2_2") (pintype "passive"))
    )
    (net (code "74") (name "Net-(IC2A--IN)") (class "Default")
      (node (ref "IC2") (pin "2") (pinfunction "-IN_2") (pintype "input"))
      (node (ref "IC4") (pin "4") (pinfunction "COM_4") (pintype "tri_state"))
      (node (ref "R6") (pin "1") (pinfunction "1_1") (pintype "passive"))
      (node (ref "R7") (pin "2") (pinfunction "2_2") (pintype "passive"))
    )
    (net (code "75") (name "Net-(IC2B-+IN)") (class "Default")
      (node (ref "IC2") (pin "5") (pinfunction "+IN_5") (pintype "input"))
      (node (ref "IC4") (pin "2") (pinfunction "COM_2") (pintype "tri_state"))
      (node (ref "R3") (pin "2") (pinfunction "S_2") (pintype "passive"))
    )
    (net (code "76") (name "Net-(IC2C--IN)") (class "Default")
      (node (ref "IC2") (pin "9") (pinfunction "-IN_9") (pintype "input"))
      (node (ref "IC4") (pin "10") (pinfunction "COM_10") (pintype "tri_state"))
      (node (ref "R12") (pin "1") (pinfunction "1_1") (pintype "passive"))
      (node (ref "R13") (pin "2") (pinfunction "2_2") (pintype "passive"))
    )
    (net (code "77") (name "Net-(IC2D--IN)") (class "Default")
      (node (ref "IC2") (pin "13") (pinfunction "-IN_13") (pintype "input"))
      (node (ref "IC4") (pin "8") (pinfunction "NO_8") (pintype "tri_state"))
      (node (ref "R18") (pin "1") (pinfunction "1_1") (pintype "passive"))
      (node (ref "R19") (pin "2") (pinfunction "2_2") (pintype "passive"))
    )
    (net (code "78") (name "Net-(IC3A-COM)") (class "Default")
      (node (ref "IC3") (pin "2") (pinfunction "COM_2") (pintype "tri_state"))
      (node (ref "R4") (pin "1") (pinfunction "1_1") (pintype "passive"))
      (node (ref "R5") (pin "1") (pinfunction "1_1") (pintype "passive"))
    )
    (net (code "79") (name "Net-(IC3B-COM)") (class "Default")
      (node (ref "IC3") (pin "4") (pinfunction "COM_4") (pintype "tri_state"))
      (node (ref "R16") (pin "1") (pinfunction "1_1") (pintype "passive"))
      (node (ref "R17") (pin "1") (pinfunction "1_1") (pintype "passive"))
    )
    (net (code "80") (name "Net-(IC3C-COM)") (class "Default")
      (node (ref "IC3") (pin "9") (pinfunction "COM_9") (pintype "tri_state"))
      (node (ref "R22") (pin "1") (pinfunction "1_1") (pintype "passive"))
      (node (ref "R23") (pin "1") (pinfunction "1_1") (pintype "passive"))
    )
    (net (code "81") (name "Net-(IC3D-NO)") (class "Default")
      (node (ref "IC3") (pin "11") (pinfunction "NO_11") (pintype "tri_state"))
      (node (ref "R10") (pin "1") (pinfunction "1_1") (pintype "passive"))
      (node (ref "R11") (pin "1") (pinfunction "1_1") (pintype "passive"))
    )
    (net (code "82") (name "Net-(IC4A-NO)") (class "Default")
      (node (ref "IC4") (pin "1") (pinfunction "NO_1") (pintype "tri_state"))
      (node (ref "R1") (pin "2") (pinfunction "2_2") (pintype "passive"))
    )
    (net (code "83") (name "Net-(IC4B-NO)") (class "Default")
      (node (ref "IC4") (pin "3") (pinfunction "NO_3") (pintype "tri_state"))
      (node (ref "R7") (pin "1") (pinfunction "1_1") (pintype "passive"))
      (node (ref "R8") (pin "1") (pinfunction "1_1") (pintype "passive"))
    )
    (net (code "84") (name "Net-(IC4C-COM)") (class "Default")
      (node (ref "IC4") (pin "9") (pinfunction "COM_9") (pintype "tri_state"))
      (node (ref "R19") (pin "1") (pinfunction "1_1") (pintype "passive"))
      (node (ref "R20") (pin "1") (pinfunction "1_1") (pintype "passive"))
    )
    (net (code "85") (name "Net-(IC4D-NO)") (class "Default")
      (node (ref "IC4") (pin "11") (pinfunction "NO_11") (pintype "tri_state"))
      (node (ref "R13") (pin "1") (pinfunction "1_1") (pintype "passive"))
      (node (ref "R14") (pin "1") (pinfunction "1_1") (pintype "passive"))
    )
    (net (code "86") (name "Net-(IC7A-+IN)") (class "Default")
      (node (ref "C8") (pin "1") (pinfunction "1_1") (pintype "passive"))
      (node (ref "IC7") (pin "3") (pinfunction "+IN_3") (pintype "input"))
      (node (ref "R34") (pin "2") (pinfunction "2_2") (pintype "passive"))
    )
    (net (code "87") (name "Net-(IC7A--IN)") (class "Default")
      (node (ref "IC7") (pin "4") (pinfunction "-IN_4") (pintype "input"))
      (node (ref "R32") (pin "1") (pinfunction "1_1") (pintype "passive"))
      (node (ref "R33") (pin "2") (pinfunction "2_2") (pintype "passive"))
    )
    (net (code "88") (name "Net-(IC8A-+IN)") (class "Default")
      (node (ref "C10") (pin "1") (pinfunction "1_1") (pintype "passive"))
      (node (ref "IC8") (pin "3") (pinfunction "+IN_3") (pintype "input"))
      (node (ref "R38") (pin "2") (pinfunction "2_2") (pintype "passive"))
    )
    (net (code "89") (name "Net-(IC8A--IN)") (class "Default")
      (node (ref "IC8") (pin "4") (pinfunction "-IN_4") (pintype "input"))
      (node (ref "R36") (pin "1") (pinfunction "1_1") (pintype "passive"))
      (node (ref "R37") (pin "2") (pinfunction "2_2") (pintype "passive"))
    )
    (net (code "90") (name "Net-(IC10A-O)") (class "Default")
      (node (ref "IC10") (pin "2") (pinfunction "O_2") (pintype "output"))
      (node (ref "R53") (pin "1") (pinfunction "1_1") (pintype "passive"))
    )
    (net (code "91") (name "Net-(IC10B-O)") (class "Default")
      (node (ref "IC10") (pin "4") (pinfunction "O_4") (pintype "output"))
      (node (ref "R41") (pin "1") (pinfunction "1_1") (pintype "passive"))
    )
    (net (code "92") (name "Net-(IC10C-O)") (class "Default")
      (node (ref "IC10") (pin "6") (pinfunction "O_6") (pintype "output"))
      (node (ref "R40") (pin "1") (pinfunction "1_1") (pintype "passive"))
    )
    (net (code "93") (name "Net-(IC10D-O)") (class "Default")
      (node (ref "IC10") (pin "10") (pinfunction "O_10") (pintype "output"))
      (node (ref "R42") (pin "1") (pinfunction "1_1") (pintype "passive"))
    )
    (net (code "94") (name "Net-(IC10E-O)") (class "Default")
      (node (ref "IC10") (pin "12") (pinfunction "O_12") (pintype "output"))
      (node (ref "R43") (pin "1") (pinfunction "1_1") (pintype "passive"))
    )
    (net (code "95") (name "Net-(IC10F-O)") (class "Default")
      (node (ref "IC10") (pin "15") (pinfunction "O_15") (pintype "output"))
      (node (ref "R52") (pin "1") (pinfunction "1_1") (pintype "passive"))
    )
    (net (code "96") (name "OE") (class "Default")
      (node (ref "74LVC245") (pin "19") (pinfunction "G_19") (pintype "input"))
      (node (ref "PCB1") (pin "P8.30") (pinfunction "P8.30_P8.30") (pintype "bidirectional"))
      (node (ref "R48") (pin "2") (pinfunction "2_2") (pintype "passive"))
    )
    (net (code "97") (name "PWM_OUT1") (class "Default")
      (node (ref "R52") (pin "2") (pinfunction "2_2") (pintype "passive"))
      (node (ref "X5") (pin "A22") (pinfunction "-22_A22") (pintype "passive"))
      (node (ref "X5") (pin "B22") (pinfunction "B-22_B22") (pintype "passive"))
    )
    (net (code "98") (name "PWM_OUT2") (class "Default")
      (node (ref "R53") (pin "2") (pinfunction "2_2") (pintype "passive"))
      (node (ref "X5") (pin "A23") (pinfunction "-23_A23") (pintype "passive"))
      (node (ref "X5") (pin "B23") (pinfunction "B-23_B23") (pintype "passive"))
    )
    (net (code "99") (name "SW_IN_BIAS") (class "Default")
      (node (ref "IC4") (pin "13") (pinfunction "IN_13") (pintype "input"))
      (node (ref "PCB1") (pin "P9.16") (pinfunction "P9.16_P9.16") (pintype "bidirectional"))
      (node (ref "R50") (pin "2") (pinfunction "2_2") (pintype "passive"))
    )
    (net (code "100") (name "SW_IN_FB") (class "Default")
      (node (ref "IC3") (pin "12") (pinfunction "IN_12") (pintype "input"))
      (node (ref "IC3") (pin "13") (pinfunction "IN_13") (pintype "input"))
      (node (ref "IC3") (pin "5") (pinfunction "IN_5") (pintype "input"))
      (node (ref "IC3") (pin "6") (pinfunction "IN_6") (pintype "input"))
      (node (ref "IC4") (pin "12") (pinfunction "IN_12") (pintype "input"))
      (node (ref "IC4") (pin "5") (pinfunction "IN_5") (pintype "input"))
      (node (ref "IC4") (pin "6") (pinfunction "IN_6") (pintype "input"))
      (node (ref "PCB1") (pin "P9.14") (pinfunction "P9.14_P9.14") (pintype "bidirectional"))
      (node (ref "R51") (pin "2") (pinfunction "2_2") (pintype "passive"))
    )
    (net (code "101") (name "V_ADC_REF") (class "Default")
      (node (ref "PCB1") (pin "P9.32") (pinfunction "P9.32_P9.32") (pintype "bidirectional"))
      (node (ref "R3") (pin "3") (pinfunction "E_3") (pintype "passive"))
    )
    (net (code "102") (name "V_OFFSET") (class "Default")
      (node (ref "C19") (pin "1") (pinfunction "1_1") (pintype "passive"))
      (node (ref "C20") (pin "1") (pinfunction "1_1") (pintype "passive"))
      (node (ref "IC1") (pin "10") (pinfunction "+IN_10") (pintype "input"))
      (node (ref "IC1") (pin "12") (pinfunction "+IN_12") (pintype "input"))
      (node (ref "IC1") (pin "3") (pinfunction "+IN_3") (pintype "input"))
      (node (ref "IC1") (pin "5") (pinfunction "+IN_5") (pintype "input"))
      (node (ref "IC2") (pin "10") (pinfunction "+IN_10") (pintype "input"))
      (node (ref "IC2") (pin "12") (pinfunction "+IN_12") (pintype "input"))
      (node (ref "IC2") (pin "3") (pinfunction "+IN_3") (pintype "input"))
      (node (ref "IC2") (pin "6") (pinfunction "-IN_6") (pintype "input"))
      (node (ref "IC2") (pin "7") (pinfunction "OUT_7") (pintype "open_collector"))
    )
    (net (code "103") (name "unconnected-(GNDA-O-Pad2)") (class "Default")
      (node (ref "GND") (pin "2") (pinfunction "O_2") (pintype "output"))
    )
    (net (code "104") (name "unconnected-(GNDB-O-Pad4)") (class "Default")
      (node (ref "GND") (pin "4") (pinfunction "O_4") (pintype "output"))
    )
    (net (code "105") (name "unconnected-(X5-B-1-PadB1)") (class "Default")
      (node (ref "X5") (pin "B1") (pinfunction "B-1_B1") (pintype "passive"))
    )
    (net (code "106") (name "unconnected-(X5-B-2-PadB2)") (class "Default")
      (node (ref "X5") (pin "B2") (pinfunction "B-2_B2") (pintype "passive"))
    )
    (net (code "107") (name "unconnected-(X5-B-3-PadB3)") (class "Default")
      (node (ref "X5") (pin "B3") (pinfunction "B-3_B3") (pintype "passive"))
    )
    (net (code "108") (name "unconnected-(X5-B-4-PadB4)") (class "Default")
      (node (ref "X5") (pin "B4") (pinfunction "B-4_B4") (pintype "passive"))
    )
    (net (code "109") (name "unconnected-(X5-B-5-PadB5)") (class "Default")
      (node (ref "X5") (pin "B5") (pinfunction "B-5_B5") (pintype "passive"))
    )
    (net (code "110") (name "unconnected-(X5-B-6-PadB6)") (class "Default")
      (node (ref "X5") (pin "B6") (pinfunction "B-6_B6") (pintype "passive"))
    )
    (net (code "111") (name "unconnected-(X5-B-7-PadB7)") (class "Default")
      (node (ref "X5") (pin "B7") (pinfunction "B-7_B7") (pintype "passive"))
    )
    (net (code "112") (name "unconnected-(X5-B-8-PadB8)") (class "Default")
      (node (ref "X5") (pin "B8") (pinfunction "B-8_B8") (pintype "passive"))
    )
  )
)
